# Shield.net
KiCad netlist of a schematic drawn in EAGLE
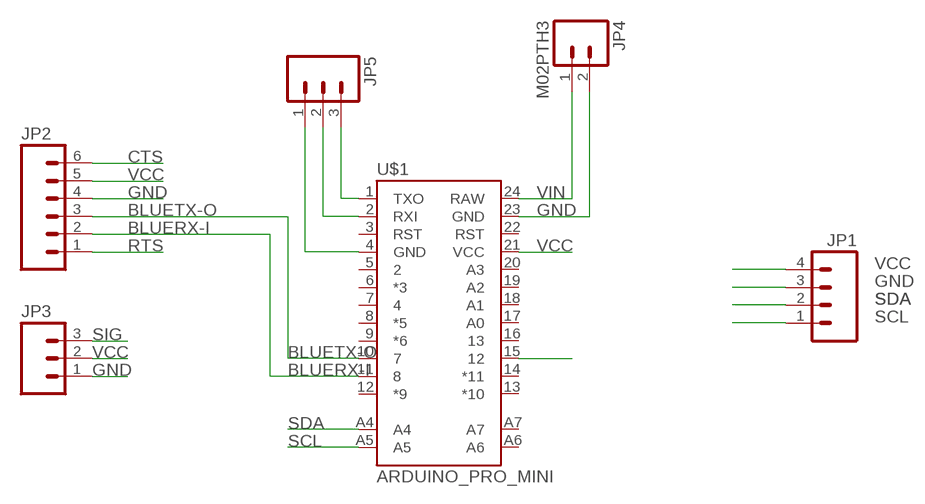
[diagram p0: schematic, sheet 1]

(export (version "E")
  (design (tool "Eeschema 10.0.6"))
  (components
    (comp (ref "JP1")
      (value "M04LONGPADS")
      (footprint "eagle-import:1X04_LONGPADS")
      (libsource (lib "eagle-import") (part "M04LONGPADS"))
    )
    (comp (ref "JP2")
      (value "M06LONGPADS")
      (footprint "eagle-import:1X06_LONGPADS")
      (libsource (lib "eagle-import") (part "M06LONGPADS"))
    )
    (comp (ref "JP3")
      (value "M03PTH")
      (footprint "eagle-import:1X03")
      (libsource (lib "eagle-import") (part "M03PTH"))
    )
    (comp (ref "JP4")
      (value "M02PTH3")
      (footprint "eagle-import:1X02_LONGPADS")
      (libsource (lib "eagle-import") (part "M02PTH3"))
    )
    (comp (ref "JP5")
      (value "M03LONGPADS")
      (footprint "eagle-import:1X03_LONGPADS")
      (libsource (lib "eagle-import") (part "M03LONGPADS"))
    )
    (comp (ref "U$1")
      (value "ARDUINO_PRO_MINI")
      (footprint "eagle-import:ARDUINO_PRO_MINI")
      (libsource (lib "eagle-import") (part "ARDUINO_PRO_MINI"))
    )
  )
  (nets
    (net (code "1") (name "/BLUERX-I") (class "Default")
      (node (ref "JP2") (pin "2") (pinfunction "2_2") (pintype "passive"))
      (node (ref "U$1") (pin "11") (pinfunction "8_11") (pintype "bidirectional"))
    )
    (net (code "2") (name "/BLUETX-O") (class "Default")
      (node (ref "JP2") (pin "3") (pinfunction "3_3") (pintype "passive"))
      (node (ref "U$1") (pin "10") (pinfunction "7_10") (pintype "bidirectional"))
    )
    (net (code "3") (name "/CTS") (class "Default")
      (node (ref "JP2") (pin "6") (pinfunction "6_6") (pintype "passive"))
    )
    (net (code "4") (name "/GND") (class "Default")
      (node (ref "JP1") (pin "3") (pinfunction "3_3") (pintype "passive"))
      (node (ref "JP2") (pin "4") (pinfunction "4_4") (pintype "passive"))
      (node (ref "JP3") (pin "1") (pinfunction "1_1") (pintype "passive"))
      (node (ref "JP4") (pin "2") (pinfunction "2_2") (pintype "passive"))
      (node (ref "JP5") (pin "1") (pinfunction "1_1") (pintype "passive"))
      (node (ref "U$1") (pin "23") (pinfunction "GND_23") (pintype "bidirectional"))
      (node (ref "U$1") (pin "4") (pinfunction "GND_4") (pintype "bidirectional"))
    )
    (net (code "5") (name "/RTS") (class "Default")
      (node (ref "JP2") (pin "1") (pinfunction "1_1") (pintype "passive"))
    )
    (net (code "6") (name "/SCL") (class "Default")
      (node (ref "JP1") (pin "1") (pinfunction "1_1") (pintype "passive"))
      (node (ref "U$1") (pin "A5") (pinfunction "A5_A5") (pintype "bidirectional"))
    )
    (net (code "7") (name "/SDA") (class "Default")
      (node (ref "JP1") (pin "2") (pinfunction "2_2") (pintype "passive"))
      (node (ref "U$1") (pin "A4") (pinfunction "A4_A4") (pintype "bidirectional"))
    )
    (net (code "8") (name "/SIG") (class "Default")
      (node (ref "JP3") (pin "3") (pinfunction "3_3") (pintype "passive"))
      (node (ref "U$1") (pin "15") (pinfunction "12_15") (pintype "bidirectional"))
    )
    (net (code "9") (name "/VCC") (class "Default")
      (node (ref "JP1") (pin "4") (pinfunction "4_4") (pintype "passive"))
      (node (ref "JP2") (pin "5") (pinfunction "5_5") (pintype "passive"))
      (node (ref "JP3") (pin "2") (pinfunction "2_2") (pintype "passive"))
      (node (ref "U$1") (pin "21") (pinfunction "VCC_21") (pintype "bidirectional"))
    )
    (net (code "10") (name "/VIN") (class "Default")
      (node (ref "JP4") (pin "1") (pinfunction "1_1") (pintype "passive"))
      (node (ref "U$1") (pin "24") (pinfunction "RAW_24") (pintype "bidirectional"))
    )
    (net (code "11") (name "Net-(U$1-RXI)") (class "Default")
      (node (ref "JP5") (pin "2") (pinfunction "2_2") (pintype "passive"))
      (node (ref "U$1") (pin "2") (pinfunction "RXI_2") (pintype "bidirectional"))
    )
    (net (code "12") (name "Net-(U$1-TXO)") (class "Default")
      (node (ref "JP5") (pin "3") (pinfunction "3_3") (pintype "passive"))
      (node (ref "U$1") (pin "1") (pinfunction "TXO_1") (pintype "bidirectional"))
    )
    (net (code "13") (name "unconnected-(U$1-*3-Pad6)") (class "Default")
      (node (ref "U$1") (pin "6") (pinfunction "*3_6") (pintype "bidirectional"))
    )
    (net (code "14") (name "unconnected-(U$1-*5-Pad8)") (class "Default")
      (node (ref "U$1") (pin "8") (pinfunction "*5_8") (pintype "bidirectional"))
    )
    (net (code "15") (name "unconnected-(U$1-*6-Pad9)") (class "Default")
      (node (ref "U$1") (pin "9") (pinfunction "*6_9") (pintype "bidirectional"))
    )
    (net (code "16") (name "unconnected-(U$1-*9-Pad12)") (class "Default")
      (node (ref "U$1") (pin "12") (pinfunction "*9_12") (pintype "bidirectional"))
    )
    (net (code "17") (name "unconnected-(U$1-*10-Pad13)") (class "Default")
      (node (ref "U$1") (pin "13") (pinfunction "*10_13") (pintype "bidirectional"))
    )
    (net (code "18") (name "unconnected-(U$1-*11-Pad14)") (class "Default")
      (node (ref "U$1") (pin "14") (pinfunction "*11_14") (pintype "bidirectional"))
    )
    (net (code "19") (name "unconnected-(U$1-2-Pad5)") (class "Default")
      (node (ref "U$1") (pin "5") (pinfunction "2_5") (pintype "bidirectional"))
    )
    (net (code "20") (name "unconnected-(U$1-4-Pad7)") (class "Default")
      (node (ref "U$1") (pin "7") (pinfunction "4_7") (pintype "bidirectional"))
    )
    (net (code "21") (name "unconnected-(U$1-13-Pad16)") (class "Default")
      (node (ref "U$1") (pin "16") (pinfunction "13_16") (pintype "bidirectional"))
    )
    (net (code "22") (name "unconnected-(U$1-A0-Pad17)") (class "Default")
      (node (ref "U$1") (pin "17") (pinfunction "A0_17") (pintype "bidirectional"))
    )
    (net (code "23") (name "unconnected-(U$1-A1-Pad18)") (class "Default")
      (node (ref "U$1") (pin "18") (pinfunction "A1_18") (pintype "bidirectional"))
    )
    (net (code "24") (name "unconnected-(U$1-A2-Pad19)") (class "Default")
      (node (ref "U$1") (pin "19") (pinfunction "A2_19") (pintype "bidirectional"))
    )
    (net (code "25") (name "unconnected-(U$1-A3-Pad20)") (class "Default")
      (node (ref "U$1") (pin "20") (pinfunction "A3_20") (pintype "bidirectional"))
    )
    (net (code "26") (name "unconnected-(U$1-PadA6)") (class "Default")
      (node (ref "U$1") (pin "A6") (pinfunction "A6_A6") (pintype "bidirectional"))
    )
    (net (code "27") (name "unconnected-(U$1-PadA7)") (class "Default")
      (node (ref "U$1") (pin "A7") (pinfunction "A7_A7") (pintype "bidirectional"))
    )
    (net (code "28") (name "unconnected-(U$1-RST-Pad3)") (class "Default")
      (node (ref "U$1") (pin "3") (pinfunction "RST_3") (pintype "bidirectional"))
    )
    (net (code "29") (name "unconnected-(U$1-RST-Pad22)") (class "Default")
      (node (ref "U$1") (pin "22") (pinfunction "RST_22") (pintype "bidirectional"))
    )
  )
)
